# MAX31855T_BREAKOUT.net
KiCad netlist of a schematic drawn in EAGLE
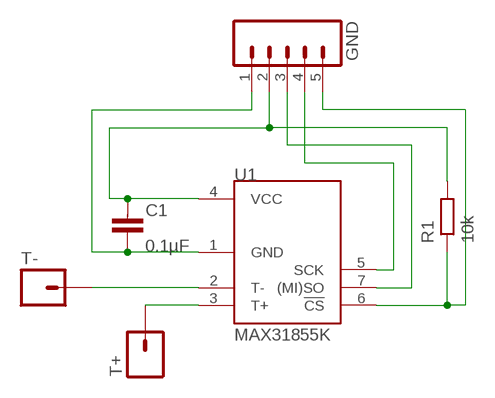
[diagram p0: schematic, sheet 1]

(export (version "E")
  (design (tool "Eeschema 10.0.6"))
  (components
    (comp (ref "C1")
      (value "0.1µF")
      (footprint "eagle-import:C0805-L")
      (libsource (lib "eagle-import") (part "CAPACITOR0805-L"))
    )
    (comp (ref "GND")
      (value "M05PTH")
      (footprint "eagle-import:1X05")
      (libsource (lib "eagle-import") (part "M05PTH"))
    )
    (comp (ref "R1")
      (value "10k")
      (footprint "eagle-import:R0603-N")
      (libsource (lib "eagle-import") (part "RESISTOR0603-N"))
    )
    (comp (ref "T+")
      (value "M01SMD")
      (footprint "eagle-import:LUXEON-PAD")
      (libsource (lib "eagle-import") (part "M01SMD"))
    )
    (comp (ref "T-")
      (value "M01SMD")
      (footprint "eagle-import:LUXEON-PAD")
      (libsource (lib "eagle-import") (part "M01SMD"))
    )
    (comp (ref "U1")
      (value "MAX31855K")
      (footprint "eagle-import:SOIC8")
      (libsource (lib "eagle-import") (part "MAX31855K"))
    )
  )
  (nets
    (net (code "1") (name "Net-(R1-P$1)") (class "Default")
      (node (ref "GND") (pin "5") (pinfunction "5_5") (pintype "passive"))
      (node (ref "R1") (pin "1") (pinfunction "P$1_1") (pintype "passive"))
      (node (ref "U1") (pin "6") (pinfunction "~{CS}_6") (pintype "bidirectional"))
    )
    (net (code "2") (name "Net-(R1-P$2)") (class "Default")
      (node (ref "C1") (pin "1") (pinfunction "1_1") (pintype "passive"))
      (node (ref "GND") (pin "2") (pinfunction "2_2") (pintype "passive"))
      (node (ref "R1") (pin "2") (pinfunction "P$2_2") (pintype "passive"))
      (node (ref "U1") (pin "4") (pinfunction "VCC_4") (pintype "bidirectional"))
    )
    (net (code "3") (name "Net-(T+-1)") (class "Default")
      (node (ref "T+") (pin "P$1") (pinfunction "1_P$1") (pintype "passive"))
      (node (ref "U1") (pin "3") (pinfunction "T+_3") (pintype "bidirectional"))
    )
    (net (code "4") (name "Net-(T--1)") (class "Default")
      (node (ref "T-") (pin "P$1") (pinfunction "1_P$1") (pintype "passive"))
      (node (ref "U1") (pin "2") (pinfunction "T-_2") (pintype "bidirectional"))
    )
    (net (code "5") (name "Net-(U1-(MI)SO)") (class "Default")
      (node (ref "GND") (pin "3") (pinfunction "3_3") (pintype "passive"))
      (node (ref "U1") (pin "7") (pinfunction "(MI)SO_7") (pintype "bidirectional"))
    )
    (net (code "6") (name "Net-(U1-GND)") (class "Default")
      (node (ref "C1") (pin "2") (pinfunction "2_2") (pintype "passive"))
      (node (ref "GND") (pin "1") (pinfunction "1_1") (pintype "passive"))
      (node (ref "U1") (pin "1") (pinfunction "GND_1") (pintype "bidirectional"))
    )
    (net (code "7") (name "Net-(U1-SCK)") (class "Default")
      (node (ref "GND") (pin "4") (pinfunction "4_4") (pintype "passive"))
      (node (ref "U1") (pin "5") (pinfunction "SCK_5") (pintype "bidirectional"))
    )
  )
)
